# Power.net
KiCad netlist of a schematic drawn in Altium Designer
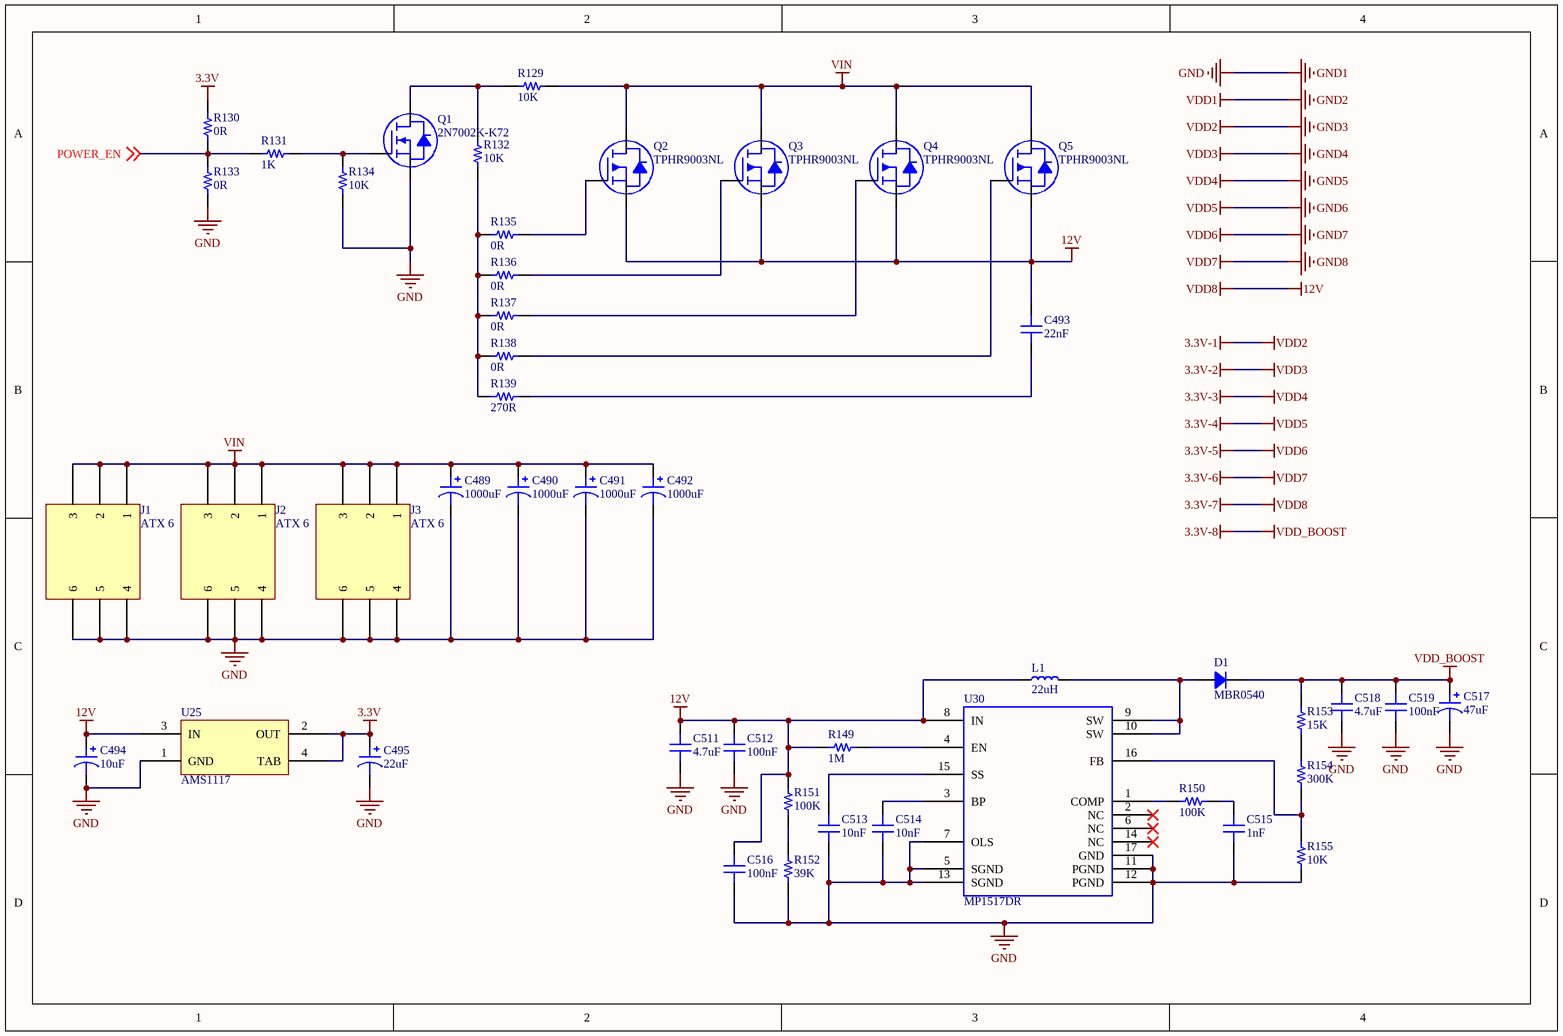
[diagram p0: Power.SchDoc]

(export (version "E")
  (design (tool "Eeschema 10.0.6"))
  (components
    (comp (ref "C489")
      (value "1000uF")
      (footprint "CAP ALUM 10.3MM")
      (libsource (lib "Miner_8TH") (part "POLARIZED CAP"))
    )
    (comp (ref "C490")
      (value "1000uF")
      (footprint "CAP ALUM 10.3MM")
      (libsource (lib "Miner_8TH") (part "POLARIZED CAP"))
    )
    (comp (ref "C491")
      (value "1000uF")
      (footprint "CAP ALUM 10.3MM")
      (libsource (lib "Miner_8TH") (part "POLARIZED CAP"))
    )
    (comp (ref "C492")
      (value "1000uF")
      (footprint "CAP ALUM 10.3MM")
      (libsource (lib "Miner_8TH") (part "POLARIZED CAP"))
    )
    (comp (ref "C493") (value "22nF") (footprint "CAP_SMD_0805") (libsource (lib "Miner_8TH") (part "CAP")))
    (comp (ref "C494")
      (value "10uF")
      (footprint "CAP-TAN-CASE-A")
      (libsource (lib "Miner_8TH") (part "POLARIZED CAP"))
    )
    (comp (ref "C495")
      (value "22uF")
      (footprint "CAP-TAN-CASE-A")
      (libsource (lib "Miner_8TH") (part "POLARIZED CAP"))
    )
    (comp (ref "C511") (value "4.7uF") (footprint "CAP_SMD_0805") (libsource (lib "Miner_8TH") (part "CAP")))
    (comp (ref "C512") (value "100nF") (footprint "CAP_SMD_0805") (libsource (lib "Miner_8TH") (part "CAP")))
    (comp (ref "C513") (value "10nF") (footprint "CAP_SMD_0805") (libsource (lib "Miner_8TH") (part "CAP")))
    (comp (ref "C514") (value "10nF") (footprint "CAP_SMD_0805") (libsource (lib "Miner_8TH") (part "CAP")))
    (comp (ref "C515") (value "1nF") (footprint "CAP_SMD_0805") (libsource (lib "Miner_8TH") (part "CAP")))
    (comp (ref "C516") (value "100nF") (footprint "CAP_SMD_0805") (libsource (lib "Miner_8TH") (part "CAP")))
    (comp (ref "C517")
      (value "47uF")
      (footprint "CAP ALUM 10.3MM")
      (libsource (lib "Miner_8TH") (part "POLARIZED CAP"))
    )
    (comp (ref "C518") (value "4.7uF") (footprint "CAP_SMD_0805") (libsource (lib "Miner_8TH") (part "CAP")))
    (comp (ref "C519") (value "100nF") (footprint "CAP_SMD_0805") (libsource (lib "Miner_8TH") (part "CAP")))
    (comp (ref "D1") (value "MBR0540") (footprint "m7") (libsource (lib "Miner_8TH") (part "1N4007")))
    (comp (ref "J1") (value "ATX 6") (footprint "ATX 6") (libsource (lib "Miner_8TH") (part "ATX 6")))
    (comp (ref "J2") (value "ATX 6") (footprint "ATX 6") (libsource (lib "Miner_8TH") (part "ATX 6")))
    (comp (ref "J3") (value "ATX 6") (footprint "ATX 6") (libsource (lib "Miner_8TH") (part "ATX 6")))
    (comp (ref "L1") (value "22uH") (footprint "IND") (libsource (lib "Miner_8TH") (part "INDUCTOR")))
    (comp (ref "Q1")
      (value "2N7002K-K72")
      (footprint "SOT-23_H")
      (libsource (lib "Miner_8TH") (part "2N70002"))
    )
    (comp (ref "Q2")
      (value "TPHR9003NL")
      (footprint "ADVANCE SOP")
      (libsource (lib "Miner_8TH") (part "MOSFET-N"))
    )
    (comp (ref "Q3")
      (value "TPHR9003NL")
      (footprint "ADVANCE SOP")
      (libsource (lib "Miner_8TH") (part "MOSFET-N"))
    )
    (comp (ref "Q4")
      (value "TPHR9003NL")
      (footprint "ADVANCE SOP")
      (libsource (lib "Miner_8TH") (part "MOSFET-N"))
    )
    (comp (ref "Q5")
      (value "TPHR9003NL")
      (footprint "ADVANCE SOP")
      (libsource (lib "Miner_8TH") (part "MOSFET-N"))
    )
    (comp (ref "R129") (value "10K") (footprint "RES-SMD-1206") (libsource (lib "Miner_8TH") (part "RES")))
    (comp (ref "R130") (value "0R") (footprint "RES-SMD-1206") (libsource (lib "Miner_8TH") (part "RES")))
    (comp (ref "R131") (value "1K") (footprint "RES-SMD-1206") (libsource (lib "Miner_8TH") (part "RES")))
    (comp (ref "R132") (value "10K") (footprint "RES-SMD-1206") (libsource (lib "Miner_8TH") (part "RES")))
    (comp (ref "R133") (value "0R") (footprint "RES-SMD-1206") (libsource (lib "Miner_8TH") (part "RES")))
    (comp (ref "R134") (value "10K") (footprint "RES-SMD-1206") (libsource (lib "Miner_8TH") (part "RES")))
    (comp (ref "R135") (value "0R") (footprint "RES-SMD-1206") (libsource (lib "Miner_8TH") (part "RES")))
    (comp (ref "R136") (value "0R") (footprint "RES-SMD-1206") (libsource (lib "Miner_8TH") (part "RES")))
    (comp (ref "R137") (value "0R") (footprint "RES-SMD-1206") (libsource (lib "Miner_8TH") (part "RES")))
    (comp (ref "R138") (value "0R") (footprint "RES-SMD-1206") (libsource (lib "Miner_8TH") (part "RES")))
    (comp (ref "R139") (value "270R") (footprint "RES-SMD-1206") (libsource (lib "Miner_8TH") (part "RES")))
    (comp (ref "R149") (value "1M") (footprint "RES-SMD-1206") (libsource (lib "Miner_8TH") (part "RES")))
    (comp (ref "R150") (value "100K") (footprint "RES-SMD-1206") (libsource (lib "Miner_8TH") (part "RES")))
    (comp (ref "R151") (value "100K") (footprint "RES-SMD-1206") (libsource (lib "Miner_8TH") (part "RES")))
    (comp (ref "R152") (value "39K") (footprint "RES-SMD-1206") (libsource (lib "Miner_8TH") (part "RES")))
    (comp (ref "R153") (value "15K") (footprint "RES-SMD-1206") (libsource (lib "Miner_8TH") (part "RES")))
    (comp (ref "R154") (value "300K") (footprint "RES-SMD-1206") (libsource (lib "Miner_8TH") (part "RES")))
    (comp (ref "R155") (value "10K") (footprint "RES-SMD-1206") (libsource (lib "Miner_8TH") (part "RES")))
    (comp (ref "U25") (value "AMS1117") (footprint "AMS1117") (libsource (lib "Miner_8TH") (part "AMS1117")))
    (comp (ref "U30")
      (value "MP1517DR")
      (footprint "QFN80P500X500X80-17N")
      (libsource (lib "Miner_8TH") (part "MP1517"))
    )
  )
  (nets
    (net (code "1") (name "3.3V") (class "Default")
      (node (ref "C495") (pin "1") (pinfunction "1_1") (pintype "passive"))
      (node (ref "R130") (pin "2") (pinfunction "2_2") (pintype "passive"))
      (node (ref "U25") (pin "2") (pinfunction "OUT_2") (pintype "passive"))
      (node (ref "U25") (pin "4") (pinfunction "TAB_4") (pintype "passive"))
    )
    (net (code "8") (name "3.3V-8") (class "Default")
      (node (ref "C517") (pin "1") (pinfunction "1_1") (pintype "passive"))
      (node (ref "C518") (pin "2") (pinfunction "2_2") (pintype "passive"))
      (node (ref "C519") (pin "2") (pinfunction "2_2") (pintype "passive"))
      (node (ref "D1") (pin "2") (pinfunction "2_2") (pintype "passive"))
      (node (ref "R153") (pin "1") (pinfunction "1_1") (pintype "passive"))
    )
    (net (code "9") (name "12V") (class "Default")
      (node (ref "C493") (pin "2") (pinfunction "2_2") (pintype "passive"))
      (node (ref "C494") (pin "1") (pinfunction "1_1") (pintype "passive"))
      (node (ref "C511") (pin "2") (pinfunction "2_2") (pintype "passive"))
      (node (ref "C512") (pin "2") (pinfunction "2_2") (pintype "passive"))
      (node (ref "C516") (pin "2") (pinfunction "2_2") (pintype "passive"))
      (node (ref "L1") (pin "1") (pinfunction "1_1") (pintype "passive"))
      (node (ref "Q2") (pin "D") (pinfunction "D_D") (pintype "passive"))
      (node (ref "Q3") (pin "D") (pinfunction "D_D") (pintype "passive"))
      (node (ref "Q4") (pin "D") (pinfunction "D_D") (pintype "passive"))
      (node (ref "Q5") (pin "D") (pinfunction "D_D") (pintype "passive"))
      (node (ref "R149") (pin "1") (pinfunction "1_1") (pintype "passive"))
      (node (ref "R151") (pin "2") (pinfunction "2_2") (pintype "passive"))
      (node (ref "U25") (pin "3") (pinfunction "IN_3") (pintype "passive"))
      (node (ref "U30") (pin "8") (pinfunction "IN_8") (pintype "passive"))
    )
    (net (code "10") (name "GND") (class "Default")
      (node (ref "C489") (pin "2") (pinfunction "2_2") (pintype "passive"))
      (node (ref "C490") (pin "2") (pinfunction "2_2") (pintype "passive"))
      (node (ref "C491") (pin "2") (pinfunction "2_2") (pintype "passive"))
      (node (ref "C492") (pin "2") (pinfunction "2_2") (pintype "passive"))
      (node (ref "C494") (pin "2") (pinfunction "2_2") (pintype "passive"))
      (node (ref "C495") (pin "2") (pinfunction "2_2") (pintype "passive"))
      (node (ref "C511") (pin "1") (pinfunction "1_1") (pintype "passive"))
      (node (ref "C512") (pin "1") (pinfunction "1_1") (pintype "passive"))
      (node (ref "C513") (pin "1") (pinfunction "1_1") (pintype "passive"))
      (node (ref "C514") (pin "1") (pinfunction "1_1") (pintype "passive"))
      (node (ref "C515") (pin "1") (pinfunction "1_1") (pintype "passive"))
      (node (ref "C516") (pin "1") (pinfunction "1_1") (pintype "passive"))
      (node (ref "C517") (pin "2") (pinfunction "2_2") (pintype "passive"))
      (node (ref "C518") (pin "1") (pinfunction "1_1") (pintype "passive"))
      (node (ref "C519") (pin "1") (pinfunction "1_1") (pintype "passive"))
      (node (ref "J1") (pin "4") (pinfunction "4_4") (pintype "passive"))
      (node (ref "J1") (pin "5") (pinfunction "5_5") (pintype "passive"))
      (node (ref "J1") (pin "6") (pinfunction "6_6") (pintype "passive"))
      (node (ref "J2") (pin "4") (pinfunction "4_4") (pintype "passive"))
      (node (ref "J2") (pin "5") (pinfunction "5_5") (pintype "passive"))
      (node (ref "J2") (pin "6") (pinfunction "6_6") (pintype "passive"))
      (node (ref "J3") (pin "4") (pinfunction "4_4") (pintype "passive"))
      (node (ref "J3") (pin "5") (pinfunction "5_5") (pintype "passive"))
      (node (ref "J3") (pin "6") (pinfunction "6_6") (pintype "passive"))
      (node (ref "Q1") (pin "2") (pinfunction "2_2") (pintype "passive"))
      (node (ref "R133") (pin "1") (pinfunction "1_1") (pintype "passive"))
      (node (ref "R134") (pin "1") (pinfunction "1_1") (pintype "passive"))
      (node (ref "R152") (pin "1") (pinfunction "1_1") (pintype "passive"))
      (node (ref "R155") (pin "2") (pinfunction "2_2") (pintype "passive"))
      (node (ref "U25") (pin "1") (pinfunction "GND_1") (pintype "passive"))
      (node (ref "U30") (pin "11") (pinfunction "PGND_11") (pintype "passive"))
      (node (ref "U30") (pin "12") (pinfunction "PGND_12") (pintype "passive"))
      (node (ref "U30") (pin "13") (pinfunction "SGND_13") (pintype "passive"))
      (node (ref "U30") (pin "17") (pinfunction "GND_17") (pintype "passive"))
      (node (ref "U30") (pin "5") (pinfunction "SGND_5") (pintype "passive"))
      (node (ref "U30") (pin "7") (pinfunction "OLS_7") (pintype "passive"))
    )
    (net (code "12") (name "Net-(C493-Pad1)") (class "Default")
      (node (ref "C493") (pin "1") (pinfunction "1_1") (pintype "passive"))
      (node (ref "R139") (pin "2") (pinfunction "2_2") (pintype "passive"))
    )
    (net (code "13") (name "Net-(C515-Pad2)") (class "Default")
      (node (ref "C515") (pin "2") (pinfunction "2_2") (pintype "passive"))
      (node (ref "R150") (pin "1") (pinfunction "1_1") (pintype "passive"))
    )
    (net (code "14") (name "Net-(D1-Pad1)") (class "Default")
      (node (ref "D1") (pin "1") (pinfunction "1_1") (pintype "passive"))
      (node (ref "L1") (pin "2") (pinfunction "2_2") (pintype "passive"))
      (node (ref "U30") (pin "10") (pinfunction "SW_10") (pintype "passive"))
      (node (ref "U30") (pin "9") (pinfunction "SW_9") (pintype "passive"))
    )
    (net (code "15") (name "Net-(Q1-Pad1)") (class "Default")
      (node (ref "Q1") (pin "1") (pinfunction "1_1") (pintype "passive"))
      (node (ref "R131") (pin "1") (pinfunction "1_1") (pintype "passive"))
      (node (ref "R134") (pin "2") (pinfunction "2_2") (pintype "passive"))
    )
    (net (code "16") (name "Net-(Q1-Pad3)") (class "Default")
      (node (ref "Q1") (pin "3") (pinfunction "3_3") (pintype "passive"))
      (node (ref "R129") (pin "1") (pinfunction "1_1") (pintype "passive"))
      (node (ref "R132") (pin "2") (pinfunction "2_2") (pintype "passive"))
    )
    (net (code "17") (name "Net-(Q2-PadG)") (class "Default")
      (node (ref "Q2") (pin "G") (pinfunction "G_G") (pintype "passive"))
      (node (ref "R135") (pin "2") (pinfunction "2_2") (pintype "passive"))
    )
    (net (code "18") (name "Net-(Q3-PadG)") (class "Default")
      (node (ref "Q3") (pin "G") (pinfunction "G_G") (pintype "passive"))
      (node (ref "R136") (pin "2") (pinfunction "2_2") (pintype "passive"))
    )
    (net (code "19") (name "Net-(Q4-PadG)") (class "Default")
      (node (ref "Q4") (pin "G") (pinfunction "G_G") (pintype "passive"))
      (node (ref "R137") (pin "2") (pinfunction "2_2") (pintype "passive"))
    )
    (net (code "20") (name "Net-(Q5-PadG)") (class "Default")
      (node (ref "Q5") (pin "G") (pinfunction "G_G") (pintype "passive"))
      (node (ref "R138") (pin "2") (pinfunction "2_2") (pintype "passive"))
    )
    (net (code "21") (name "Net-(R132-Pad1)") (class "Default")
      (node (ref "R132") (pin "1") (pinfunction "1_1") (pintype "passive"))
      (node (ref "R135") (pin "1") (pinfunction "1_1") (pintype "passive"))
      (node (ref "R136") (pin "1") (pinfunction "1_1") (pintype "passive"))
      (node (ref "R137") (pin "1") (pinfunction "1_1") (pintype "passive"))
      (node (ref "R138") (pin "1") (pinfunction "1_1") (pintype "passive"))
      (node (ref "R139") (pin "1") (pinfunction "1_1") (pintype "passive"))
    )
    (net (code "22") (name "Net-(R151-Pad1)") (class "Default")
      (node (ref "R151") (pin "1") (pinfunction "1_1") (pintype "passive"))
      (node (ref "R152") (pin "2") (pinfunction "2_2") (pintype "passive"))
    )
    (net (code "23") (name "Net-(R153-Pad2)") (class "Default")
      (node (ref "R153") (pin "2") (pinfunction "2_2") (pintype "passive"))
      (node (ref "R154") (pin "1") (pinfunction "1_1") (pintype "passive"))
    )
    (net (code "24") (name "Net-(U30-BP)") (class "Default")
      (node (ref "C514") (pin "2") (pinfunction "2_2") (pintype "passive"))
      (node (ref "U30") (pin "3") (pinfunction "BP_3") (pintype "passive"))
    )
    (net (code "25") (name "Net-(U30-COMP)") (class "Default")
      (node (ref "R150") (pin "2") (pinfunction "2_2") (pintype "passive"))
      (node (ref "U30") (pin "1") (pinfunction "COMP_1") (pintype "passive"))
    )
    (net (code "26") (name "Net-(U30-EN)") (class "Default")
      (node (ref "R149") (pin "2") (pinfunction "2_2") (pintype "passive"))
      (node (ref "U30") (pin "4") (pinfunction "EN_4") (pintype "passive"))
    )
    (net (code "27") (name "Net-(U30-FB)") (class "Default")
      (node (ref "R154") (pin "2") (pinfunction "2_2") (pintype "passive"))
      (node (ref "R155") (pin "1") (pinfunction "1_1") (pintype "passive"))
      (node (ref "U30") (pin "16") (pinfunction "FB_16") (pintype "passive"))
    )
    (net (code "28") (name "Net-(U30-SS)") (class "Default")
      (node (ref "C513") (pin "2") (pinfunction "2_2") (pintype "passive"))
      (node (ref "U30") (pin "15") (pinfunction "SS_15") (pintype "passive"))
    )
    (net (code "29") (name "POWER_EN") (class "Default")
      (node (ref "R130") (pin "1") (pinfunction "1_1") (pintype "passive"))
      (node (ref "R131") (pin "2") (pinfunction "2_2") (pintype "passive"))
      (node (ref "R133") (pin "2") (pinfunction "2_2") (pintype "passive"))
    )
    (net (code "30") (name "VIN") (class "Default")
      (node (ref "C489") (pin "1") (pinfunction "1_1") (pintype "passive"))
      (node (ref "C490") (pin "1") (pinfunction "1_1") (pintype "passive"))
      (node (ref "C491") (pin "1") (pinfunction "1_1") (pintype "passive"))
      (node (ref "C492") (pin "1") (pinfunction "1_1") (pintype "passive"))
      (node (ref "J1") (pin "1") (pinfunction "1_1") (pintype "passive"))
      (node (ref "J1") (pin "2") (pinfunction "2_2") (pintype "passive"))
      (node (ref "J1") (pin "3") (pinfunction "3_3") (pintype "passive"))
      (node (ref "J2") (pin "1") (pinfunction "1_1") (pintype "passive"))
      (node (ref "J2") (pin "2") (pinfunction "2_2") (pintype "passive"))
      (node (ref "J2") (pin "3") (pinfunction "3_3") (pintype "passive"))
      (node (ref "J3") (pin "1") (pinfunction "1_1") (pintype "passive"))
      (node (ref "J3") (pin "2") (pinfunction "2_2") (pintype "passive"))
      (node (ref "J3") (pin "3") (pinfunction "3_3") (pintype "passive"))
      (node (ref "Q2") (pin "S") (pinfunction "S_S") (pintype "passive"))
      (node (ref "Q3") (pin "S") (pinfunction "S_S") (pintype "passive"))
      (node (ref "Q4") (pin "S") (pinfunction "S_S") (pintype "passive"))
      (node (ref "Q5") (pin "S") (pinfunction "S_S") (pintype "passive"))
      (node (ref "R129") (pin "2") (pinfunction "2_2") (pintype "passive"))
    )
    (net (code "31") (name "unconnected-(U30-NC-Pad2)") (class "Default")
      (node (ref "U30") (pin "2") (pinfunction "NC_2") (pintype "passive+no_connect"))
    )
    (net (code "32") (name "unconnected-(U30-NC-Pad6)") (class "Default")
      (node (ref "U30") (pin "6") (pinfunction "NC_6") (pintype "passive+no_connect"))
    )
    (net (code "33") (name "unconnected-(U30-NC-Pad14)") (class "Default")
      (node (ref "U30") (pin "14") (pinfunction "NC_14") (pintype "passive+no_connect"))
    )
  )
)
